# 01-POWER.net
KiCad netlist of a schematic drawn in Altium Designer
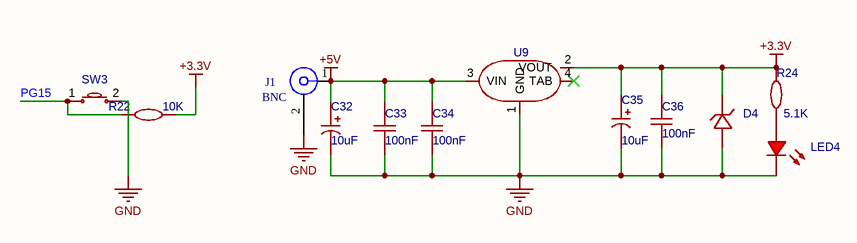
[diagram p0: 01-POWER.SchDoc]

(export (version "E")
  (design (tool "Eeschema 10.0.6"))
  (components
    (comp (ref "C32")
      (value "10uF")
      (footprint "CAP-SMD_L3.5-W2.8")
      (description "容值:4.7uF;精度:±10%;额定电压:16V;等效串联电阻:3.5Ω@100kHz;")
      (fields
        (field (name "MANUFACTURER") "TORCH(火炬)")
        (field (name "MANUFACTURERPART") "CA45-B-16V-4.7μF-K")
      )
      (libsource (lib "altium-import") (part "root_3_CA45-B-16V-4.7μF-K_"))
    )
    (comp (ref "C33")
      (value "100nF")
      (footprint "C0603")
      (fields (field (name "Comment") "CAP_0603"))
      (libsource (lib "altium-import") (part "root_1_CAP_0603_"))
    )
    (comp (ref "C34")
      (value "100nF")
      (footprint "C0603")
      (fields (field (name "Comment") "CAP_0603"))
      (libsource (lib "altium-import") (part "root_1_CAP_0603_"))
    )
    (comp (ref "C35")
      (value "10uF")
      (footprint "CAP-SMD_L3.5-W2.8")
      (description "容值:4.7uF;精度:±10%;额定电压:16V;等效串联电阻:3.5Ω@100kHz;")
      (fields
        (field (name "MANUFACTURER") "TORCH(火炬)")
        (field (name "MANUFACTURERPART") "CA45-B-16V-4.7μF-K")
      )
      (libsource (lib "altium-import") (part "root_3_CA45-B-16V-4.7μF-K_"))
    )
    (comp (ref "C36")
      (value "100nF")
      (footprint "C0603")
      (fields (field (name "Comment") "CAP_0603"))
      (libsource (lib "altium-import") (part "root_1_CAP_0603_"))
    )
    (comp (ref "D4")
      (value "SMBJ3.3A_C362089")
      (footprint "SMB_L4.6-W3.6-LS5.3-RD")
      (description "反向截止电压(Vrwm):3.3V;击穿电压:4.1V;最大钳位电压:7.3V;")
      (fields (field (name "MANUFACTURER") "JKSEMI(金开盛)") (field (name "MANUFACTURERPART") "SMBJ3.3A"))
      (libsource (lib "altium-import") (part "root_3_SMBJ3.3A_C362089_"))
    )
    (comp (ref "J1")
      (value "BNC")
      (footprint "DC-005B")
      (fields (field (name "SOURCE_PATH") "C:\\PROGRAM FILES\\印院出品\\CAPTURE 16.2\\LIBRARY\\CONNECTOR.OLB"))
      (libsource (lib "VIDEO_Demo_Kit_1") (part "BNC"))
    )
    (comp (ref "LED4")
      (value "LED_0603-R")
      (footprint "LED_0603")
      (libsource (lib "altium-import") (part "root_3_LED_0603-R_"))
    )
    (comp (ref "R22")
      (value "10K")
      (footprint "R0603")
      (fields (field (name "Comment") "Res_0603"))
      (libsource (lib "altium-import") (part "root_2_Res_0603_"))
    )
    (comp (ref "R24")
      (value "5.1K")
      (footprint "R0603")
      (fields (field (name "Comment") "Res_0603"))
      (libsource (lib "altium-import") (part "root_3_Res_0603_"))
    )
    (comp (ref "SW3")
      (value "~")
      (footprint "Key_SMD_3.6x6.1x2.5")
      (libsource (lib "altium-import") (part "root_0_Key_SMD_3.6x6.1x2.5_"))
    )
    (comp (ref "U9")
      (value "AMS1117")
      (footprint "SOT_223")
      (libsource (lib "altium-import") (part "root_0_AMS1117_"))
    )
  )
  (nets
    (net (code "1") (name "+3.3V") (class "Default")
      (node (ref "C35") (pin "1") (pinfunction "1_1") (pintype "passive"))
      (node (ref "C36") (pin "2") (pinfunction "2_2") (pintype "passive"))
      (node (ref "D4") (pin "1") (pinfunction "1_1") (pintype "passive"))
      (node (ref "R22") (pin "1") (pinfunction "1_1") (pintype "passive"))
      (node (ref "R24") (pin "1") (pinfunction "1_1") (pintype "passive"))
      (node (ref "U9") (pin "2") (pinfunction "VOUT_2") (pintype "passive"))
    )
    (net (code "2") (name "+5V") (class "Default")
      (node (ref "C32") (pin "1") (pinfunction "1_1") (pintype "passive"))
      (node (ref "C33") (pin "2") (pinfunction "2_2") (pintype "passive"))
      (node (ref "C34") (pin "2") (pinfunction "2_2") (pintype "passive"))
      (node (ref "J1") (pin "1") (pinfunction "CENTER_1") (pintype "passive"))
      (node (ref "U9") (pin "3") (pinfunction "VIN_3") (pintype "passive"))
    )
    (net (code "3") (name "/PG15") (class "Default")
      (node (ref "R22") (pin "2") (pinfunction "2_2") (pintype "passive"))
      (node (ref "SW3") (pin "1") (pinfunction "1_1") (pintype "passive"))
    )
    (net (code "4") (name "GND") (class "Default")
      (node (ref "C32") (pin "2") (pinfunction "2_2") (pintype "passive"))
      (node (ref "C33") (pin "1") (pinfunction "1_1") (pintype "passive"))
      (node (ref "C34") (pin "1") (pinfunction "1_1") (pintype "passive"))
      (node (ref "C35") (pin "2") (pinfunction "2_2") (pintype "passive"))
      (node (ref "C36") (pin "1") (pinfunction "1_1") (pintype "passive"))
      (node (ref "D4") (pin "2") (pinfunction "2_2") (pintype "passive"))
      (node (ref "J1") (pin "2") (pinfunction "SHIELD_2") (pintype "passive"))
      (node (ref "LED4") (pin "1") (pinfunction "C_1") (pintype "passive"))
      (node (ref "SW3") (pin "2") (pinfunction "2_2") (pintype "passive"))
      (node (ref "U9") (pin "1") (pinfunction "GND_1") (pintype "passive"))
    )
    (net (code "5") (name "Net-(LED4-A)") (class "Default")
      (node (ref "LED4") (pin "2") (pinfunction "A_2") (pintype "passive"))
      (node (ref "R24") (pin "2") (pinfunction "2_2") (pintype "passive"))
    )
    (net (code "6") (name "unconnected-(U9-TAB-Pad4)") (class "Default")
      (node (ref "U9") (pin "4") (pinfunction "TAB_4") (pintype "passive+no_connect"))
    )
  )
)
